# ExploraRoverRobot_DistanceSensorSystem.net
KiCad netlist of a schematic drawn in EAGLE
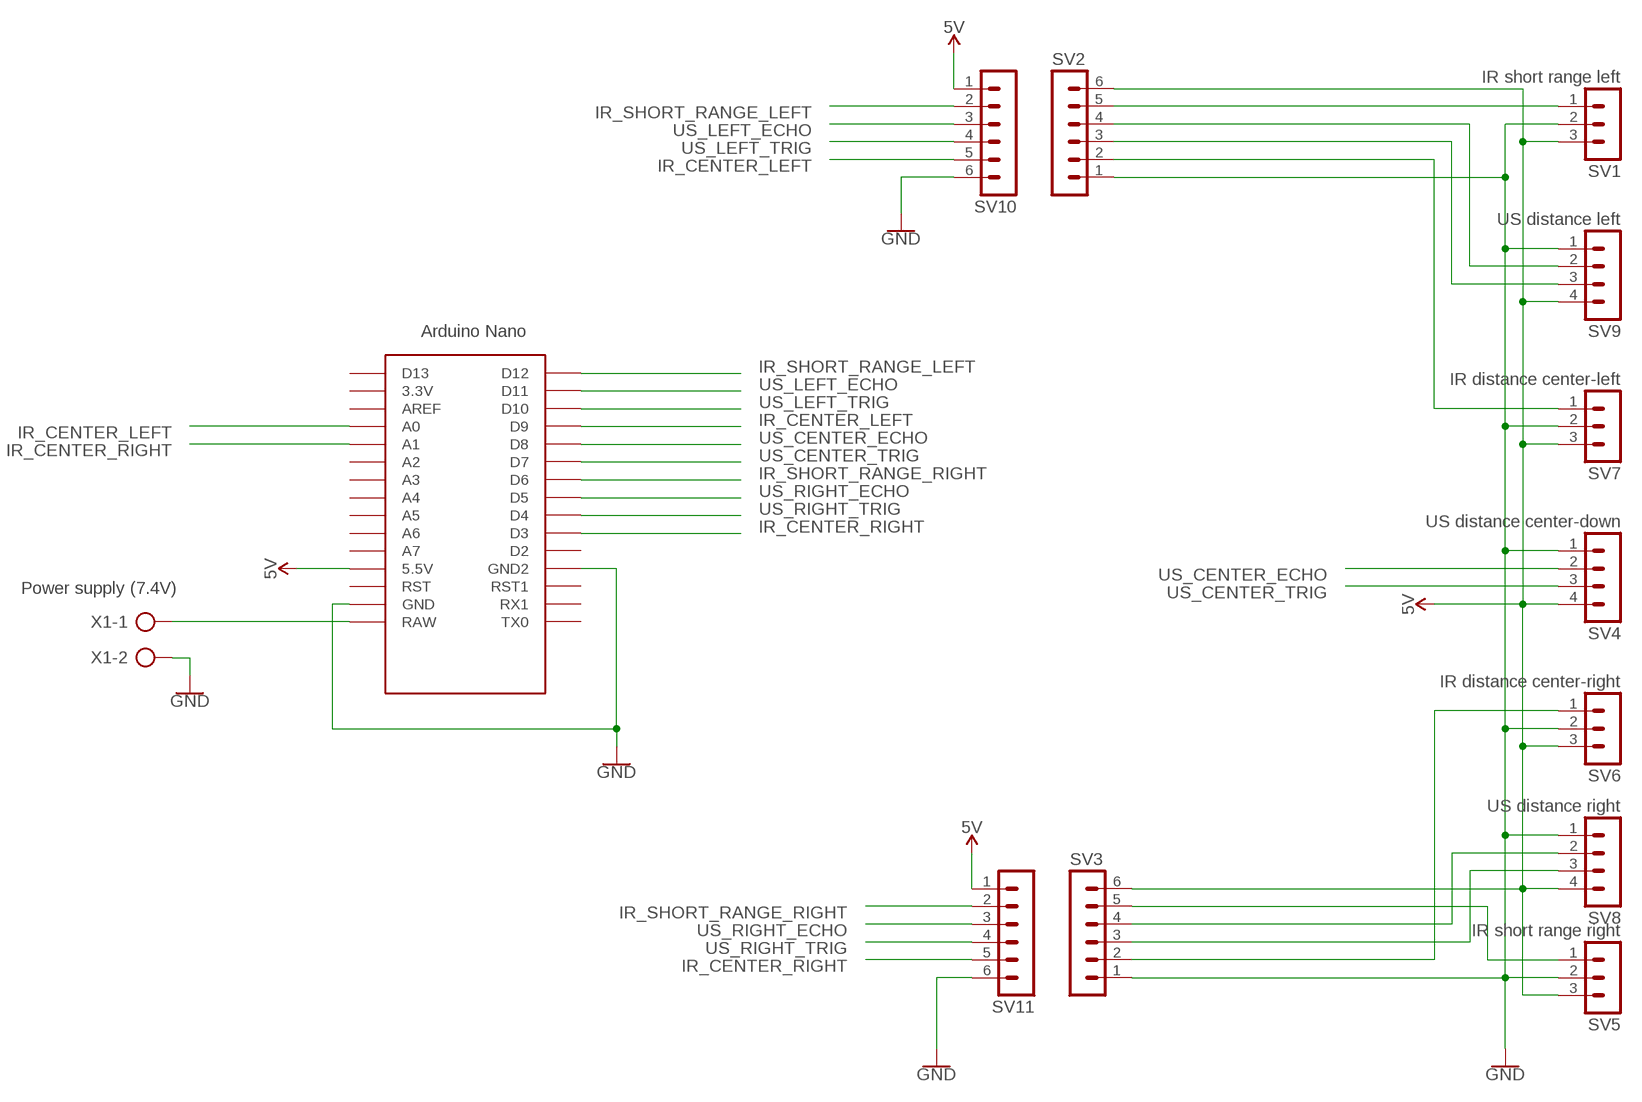
[diagram p0: schematic, sheet 1]

(export (version "E")
  (design (tool "Eeschema 10.0.6"))
  (components
    (comp (ref "SV1")
      (value "IR short range left")
      (footprint "eagle-import:MA03-1")
      (libsource (lib "eagle-import") (part "MA03-1"))
    )
    (comp (ref "SV2")
      (value "MA06-1")
      (footprint "eagle-import:MA06-1")
      (libsource (lib "eagle-import") (part "MA06-1"))
    )
    (comp (ref "SV3")
      (value "MA06-1")
      (footprint "eagle-import:MA06-1")
      (libsource (lib "eagle-import") (part "MA06-1"))
    )
    (comp (ref "SV4")
      (value "US distance center-down")
      (footprint "eagle-import:MA04-1")
      (libsource (lib "eagle-import") (part "MA04-1"))
    )
    (comp (ref "SV5")
      (value "IR short range right")
      (footprint "eagle-import:MA03-1")
      (libsource (lib "eagle-import") (part "MA03-1"))
    )
    (comp (ref "SV6")
      (value "IR distance center-right")
      (footprint "eagle-import:MA03-1")
      (libsource (lib "eagle-import") (part "MA03-1"))
    )
    (comp (ref "SV7")
      (value "IR distance center-left")
      (footprint "eagle-import:MA03-1")
      (libsource (lib "eagle-import") (part "MA03-1"))
    )
    (comp (ref "SV8")
      (value "US distance right")
      (footprint "eagle-import:MA04-1")
      (libsource (lib "eagle-import") (part "MA04-1"))
    )
    (comp (ref "SV9")
      (value "US distance left")
      (footprint "eagle-import:MA04-1")
      (libsource (lib "eagle-import") (part "MA04-1"))
    )
    (comp (ref "SV10")
      (value "MA06-1")
      (footprint "eagle-import:MA06-1")
      (libsource (lib "eagle-import") (part "MA06-1"))
    )
    (comp (ref "SV11")
      (value "MA06-1")
      (footprint "eagle-import:MA06-1")
      (libsource (lib "eagle-import") (part "MA06-1"))
    )
    (comp (ref "U$1")
      (value "NANO")
      (footprint "eagle-import:NANO")
      (libsource (lib "eagle-import") (part "NANO"))
    )
    (comp (ref "X1")
      (value "Power supply (7.4V)")
      (footprint "eagle-import:AK500_2")
      (libsource (lib "eagle-import") (part "AK500/2"))
    )
  )
  (nets
    (net (code "1") (name "/IR_CENTER_LEFT") (class "Default")
      (node (ref "SV10") (pin "5") (pinfunction "5_5") (pintype "passive"))
      (node (ref "U$1") (pin "A0") (pinfunction "A0_A0") (pintype "bidirectional"))
      (node (ref "U$1") (pin "D9") (pinfunction "D9_D9") (pintype "bidirectional"))
    )
    (net (code "2") (name "/IR_CENTER_RIGHT") (class "Default")
      (node (ref "SV11") (pin "5") (pinfunction "5_5") (pintype "passive"))
      (node (ref "U$1") (pin "A1") (pinfunction "A1_A1") (pintype "bidirectional"))
      (node (ref "U$1") (pin "D3") (pinfunction "D3_D3") (pintype "bidirectional"))
    )
    (net (code "3") (name "/IR_SHORT_RANGE_LEFT") (class "Default")
      (node (ref "SV10") (pin "2") (pinfunction "2_2") (pintype "passive"))
      (node (ref "U$1") (pin "D12") (pinfunction "D12_D12") (pintype "bidirectional"))
    )
    (net (code "4") (name "/IR_SHORT_RANGE_RIGHT") (class "Default")
      (node (ref "SV11") (pin "2") (pinfunction "2_2") (pintype "passive"))
      (node (ref "U$1") (pin "D6") (pinfunction "D6_D6") (pintype "bidirectional"))
    )
    (net (code "5") (name "/US_CENTER_ECHO") (class "Default")
      (node (ref "SV4") (pin "2") (pinfunction "2_2") (pintype "passive"))
      (node (ref "U$1") (pin "D8") (pinfunction "D8_D8") (pintype "bidirectional"))
    )
    (net (code "6") (name "/US_CENTER_TRIG") (class "Default")
      (node (ref "SV4") (pin "3") (pinfunction "3_3") (pintype "passive"))
      (node (ref "U$1") (pin "D7") (pinfunction "D7_D7") (pintype "bidirectional"))
    )
    (net (code "7") (name "/US_LEFT_ECHO") (class "Default")
      (node (ref "SV10") (pin "3") (pinfunction "3_3") (pintype "passive"))
      (node (ref "U$1") (pin "D11") (pinfunction "D11_D11") (pintype "bidirectional"))
    )
    (net (code "8") (name "/US_LEFT_TRIG") (class "Default")
      (node (ref "SV10") (pin "4") (pinfunction "4_4") (pintype "passive"))
      (node (ref "U$1") (pin "D10") (pinfunction "D10_D10") (pintype "bidirectional"))
    )
    (net (code "9") (name "/US_RIGHT_ECHO") (class "Default")
      (node (ref "SV11") (pin "3") (pinfunction "3_3") (pintype "passive"))
      (node (ref "U$1") (pin "D5") (pinfunction "D5_D5") (pintype "bidirectional"))
    )
    (net (code "10") (name "/US_RIGHT_TRIG") (class "Default")
      (node (ref "SV11") (pin "4") (pinfunction "4_4") (pintype "passive"))
      (node (ref "U$1") (pin "D4") (pinfunction "D4_D4") (pintype "bidirectional"))
    )
    (net (code "11") (name "5V") (class "Default")
      (node (ref "SV1") (pin "3") (pinfunction "3_3") (pintype "passive"))
      (node (ref "SV10") (pin "1") (pinfunction "1_1") (pintype "passive"))
      (node (ref "SV11") (pin "1") (pinfunction "1_1") (pintype "passive"))
      (node (ref "SV2") (pin "6") (pinfunction "6_6") (pintype "passive"))
      (node (ref "SV3") (pin "6") (pinfunction "6_6") (pintype "passive"))
      (node (ref "SV4") (pin "4") (pinfunction "4_4") (pintype "passive"))
      (node (ref "SV5") (pin "3") (pinfunction "3_3") (pintype "passive"))
      (node (ref "SV6") (pin "3") (pinfunction "3_3") (pintype "passive"))
      (node (ref "SV7") (pin "3") (pinfunction "3_3") (pintype "passive"))
      (node (ref "SV8") (pin "4") (pinfunction "4_4") (pintype "passive"))
      (node (ref "SV9") (pin "4") (pinfunction "4_4") (pintype "passive"))
      (node (ref "U$1") (pin "5V") (pinfunction "5.5V_5V") (pintype "bidirectional"))
    )
    (net (code "12") (name "GND") (class "Default")
      (node (ref "SV1") (pin "2") (pinfunction "2_2") (pintype "passive"))
      (node (ref "SV10") (pin "6") (pinfunction "6_6") (pintype "passive"))
      (node (ref "SV11") (pin "6") (pinfunction "6_6") (pintype "passive"))
      (node (ref "SV2") (pin "1") (pinfunction "1_1") (pintype "passive"))
      (node (ref "SV3") (pin "1") (pinfunction "1_1") (pintype "passive"))
      (node (ref "SV4") (pin "1") (pinfunction "1_1") (pintype "passive"))
      (node (ref "SV5") (pin "2") (pinfunction "2_2") (pintype "passive"))
      (node (ref "SV6") (pin "2") (pinfunction "2_2") (pintype "passive"))
      (node (ref "SV7") (pin "2") (pinfunction "2_2") (pintype "passive"))
      (node (ref "SV8") (pin "1") (pinfunction "1_1") (pintype "passive"))
      (node (ref "SV9") (pin "1") (pinfunction "1_1") (pintype "passive"))
      (node (ref "U$1") (pin "GND") (pinfunction "GND_GND") (pintype "bidirectional"))
      (node (ref "U$1") (pin "GND1") (pinfunction "GND2_GND1") (pintype "bidirectional"))
      (node (ref "X1") (pin "2") (pinfunction "KL_2") (pintype "passive"))
    )
    (net (code "13") (name "Net-(SV1-Pad1)") (class "Default")
      (node (ref "SV1") (pin "1") (pinfunction "1_1") (pintype "passive"))
      (node (ref "SV2") (pin "5") (pinfunction "5_5") (pintype "passive"))
    )
    (net (code "14") (name "Net-(SV2-Pad2)") (class "Default")
      (node (ref "SV2") (pin "2") (pinfunction "2_2") (pintype "passive"))
      (node (ref "SV7") (pin "1") (pinfunction "1_1") (pintype "passive"))
    )
    (net (code "15") (name "Net-(SV2-Pad3)") (class "Default")
      (node (ref "SV2") (pin "3") (pinfunction "3_3") (pintype "passive"))
      (node (ref "SV9") (pin "3") (pinfunction "3_3") (pintype "passive"))
    )
    (net (code "16") (name "Net-(SV2-Pad4)") (class "Default")
      (node (ref "SV2") (pin "4") (pinfunction "4_4") (pintype "passive"))
      (node (ref "SV9") (pin "2") (pinfunction "2_2") (pintype "passive"))
    )
    (net (code "17") (name "Net-(SV3-Pad2)") (class "Default")
      (node (ref "SV3") (pin "2") (pinfunction "2_2") (pintype "passive"))
      (node (ref "SV6") (pin "1") (pinfunction "1_1") (pintype "passive"))
    )
    (net (code "18") (name "Net-(SV3-Pad3)") (class "Default")
      (node (ref "SV3") (pin "3") (pinfunction "3_3") (pintype "passive"))
      (node (ref "SV8") (pin "3") (pinfunction "3_3") (pintype "passive"))
    )
    (net (code "19") (name "Net-(SV3-Pad4)") (class "Default")
      (node (ref "SV3") (pin "4") (pinfunction "4_4") (pintype "passive"))
      (node (ref "SV8") (pin "2") (pinfunction "2_2") (pintype "passive"))
    )
    (net (code "20") (name "Net-(SV3-Pad5)") (class "Default")
      (node (ref "SV3") (pin "5") (pinfunction "5_5") (pintype "passive"))
      (node (ref "SV5") (pin "1") (pinfunction "1_1") (pintype "passive"))
    )
    (net (code "21") (name "Net-(X1A-KL)") (class "Default")
      (node (ref "U$1") (pin "RAW") (pinfunction "RAW_RAW") (pintype "bidirectional"))
      (node (ref "X1") (pin "1") (pinfunction "KL_1") (pintype "passive"))
    )
    (net (code "22") (name "unconnected-(U$1-Pad3.3V)") (class "Default")
      (node (ref "U$1") (pin "3.3V") (pinfunction "3.3V_3.3V") (pintype "bidirectional"))
    )
    (net (code "23") (name "unconnected-(U$1-PadA2)") (class "Default")
      (node (ref "U$1") (pin "A2") (pinfunction "A2_A2") (pintype "bidirectional"))
    )
    (net (code "24") (name "unconnected-(U$1-PadA3)") (class "Default")
      (node (ref "U$1") (pin "A3") (pinfunction "A3_A3") (pintype "bidirectional"))
    )
    (net (code "25") (name "unconnected-(U$1-PadA4)") (class "Default")
      (node (ref "U$1") (pin "A4") (pinfunction "A4_A4") (pintype "bidirectional"))
    )
    (net (code "26") (name "unconnected-(U$1-PadA5)") (class "Default")
      (node (ref "U$1") (pin "A5") (pinfunction "A5_A5") (pintype "bidirectional"))
    )
    (net (code "27") (name "unconnected-(U$1-PadA6)") (class "Default")
      (node (ref "U$1") (pin "A6") (pinfunction "A6_A6") (pintype "bidirectional"))
    )
    (net (code "28") (name "unconnected-(U$1-PadA7)") (class "Default")
      (node (ref "U$1") (pin "A7") (pinfunction "A7_A7") (pintype "bidirectional"))
    )
    (net (code "29") (name "unconnected-(U$1-PadAREF)") (class "Default")
      (node (ref "U$1") (pin "AREF") (pinfunction "AREF_AREF") (pintype "bidirectional"))
    )
    (net (code "30") (name "unconnected-(U$1-PadD2)") (class "Default")
      (node (ref "U$1") (pin "D2") (pinfunction "D2_D2") (pintype "bidirectional"))
    )
    (net (code "31") (name "unconnected-(U$1-PadD13)") (class "Default")
      (node (ref "U$1") (pin "D13") (pinfunction "D13_D13") (pintype "bidirectional"))
    )
    (net (code "32") (name "unconnected-(U$1-PadICSP1)") (class "Default")
      (node (ref "U$1") (pin "ICSP1") (pinfunction "ICSP1_ICSP1") (pintype "bidirectional"))
    )
    (net (code "33") (name "unconnected-(U$1-PadICSP2)") (class "Default")
      (node (ref "U$1") (pin "ICSP2") (pinfunction "ICSP2_ICSP2") (pintype "bidirectional"))
    )
    (net (code "34") (name "unconnected-(U$1-PadICSP3)") (class "Default")
      (node (ref "U$1") (pin "ICSP3") (pinfunction "ICSP3_ICSP3") (pintype "bidirectional"))
    )
    (net (code "35") (name "unconnected-(U$1-PadICSP4)") (class "Default")
      (node (ref "U$1") (pin "ICSP4") (pinfunction "ICSP4_ICSP4") (pintype "bidirectional"))
    )
    (net (code "36") (name "unconnected-(U$1-PadICSP5)") (class "Default")
      (node (ref "U$1") (pin "ICSP5") (pinfunction "ICSP5_ICSP5") (pintype "bidirectional"))
    )
    (net (code "37") (name "unconnected-(U$1-PadICSP6)") (class "Default")
      (node (ref "U$1") (pin "ICSP6") (pinfunction "ICSP6_ICSP6") (pintype "bidirectional"))
    )
    (net (code "38") (name "unconnected-(U$1-PadRST)") (class "Default")
      (node (ref "U$1") (pin "RST") (pinfunction "RST_RST") (pintype "bidirectional"))
    )
    (net (code "39") (name "unconnected-(U$1-PadRST1)") (class "Default")
      (node (ref "U$1") (pin "RST1") (pinfunction "RST1_RST1") (pintype "bidirectional"))
    )
    (net (code "40") (name "unconnected-(U$1-PadRX1)") (class "Default")
      (node (ref "U$1") (pin "RX1") (pinfunction "RX1_RX1") (pintype "bidirectional"))
    )
    (net (code "41") (name "unconnected-(U$1-PadTX0)") (class "Default")
      (node (ref "U$1") (pin "TX0") (pinfunction "TX0_TX0") (pintype "bidirectional"))
    )
  )
)
